# Input-Battery.net
KiCad netlist of a schematic drawn in Altium Designer
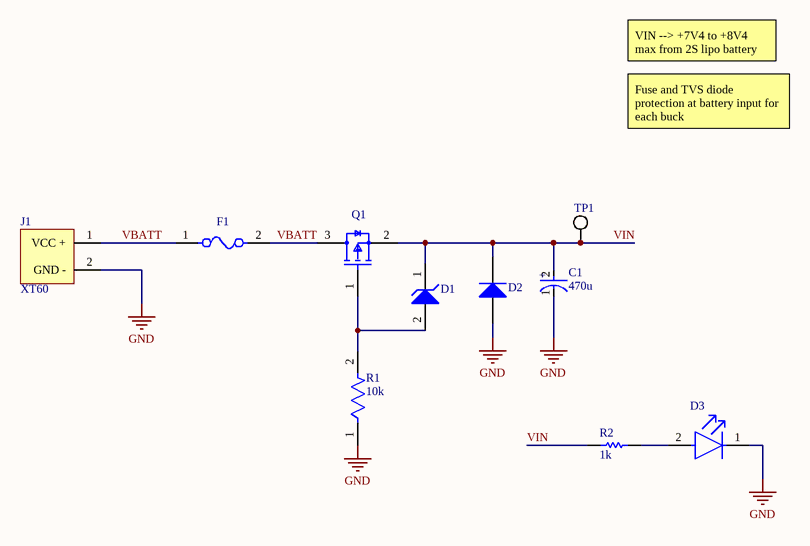
[diagram p0: Input-Battery.SchDoc]

(export (version "E")
  (design (tool "Eeschema 10.0.6"))
  (components
    (comp (ref "C1")
      (value "470u")
      (footprint "FP-RAD-TH-D_10_0_5-L_12_5-MFG")
      (description "Aluminum Electrolytic Capacitors (Radial Lead Type) 470uF ±20% 16V")
      (fields (field (name "TOLERANCE") "20%"))
      (libsource (lib "Altium Content Vault") (part "203bc49f2ac43e59fd269a8c329ed05"))
    )
    (comp (ref "D1")
      (value "MMSZ12T1G")
      (footprint "ONSC-SOD-123-2-425-04_V")
      (description "Zener Voltage Regulator, 500 mW, 2-Pin SOD-123, Pb-Free, Tape and Reel")
      (fields (field (name "MANUFACTURER") "On Semiconductor"))
      (libsource (lib "Altium Content Vault") (part "ONSC-K1A2-2"))
    )
    (comp (ref "D2")
      (value "SMAJ10A-E3/61")
      (footprint "VISH-DO-214AC-2_L")
      (fields (field (name "MANUFACTURER") "Vishay Semiconductor"))
      (libsource (lib "Altium Content Vault") (part "VISH-K1A2-2"))
    )
    (comp (ref "D3")
      (value "598-8270-107F")
      (footprint "FP-598-8270-107F-MFG")
      (description "SM LED 1206 ALINGAP G 7 REEL")
      (libsource (lib "Altium Content Vault") (part "8706943c75ba83719d021d2fdc84c58"))
    )
    (comp (ref "F1")
      (value "0452004.MRL")
      (footprint "FP-0452-MFG")
      (description "FUSE BRD MNT 4A 125VAC/VDC 2SMD")
      (fields
        (field (name "MANUFACTURER") "Littelfuse Inc")
        (field (name "OCTOPART") "https://octopart.com/0452004.mrl-littelfuse-566421")
      )
      (libsource (lib "Altium Content Vault") (part "5bcf9b9f640e542cf0359d10258e979"))
    )
    (comp (ref "J1")
      (value "XT60")
      (footprint "XT60-Footprint-1")
      (description "Connector for Lipo Batteries with XT60 connectors")
      (libsource (lib "University of California, Riverside") (part "XT60"))
    )
    (comp (ref "Q1")
      (value "DMP3099L-13")
      (footprint "FP-SOT23-IPC_A")
      (description "MOSFET P-CH 30V 3.8A SOT23")
      (libsource (lib "Altium Content Vault") (part "638227d500694eacab38e5d89898fd4"))
    )
    (comp (ref "R1")
      (value "10k")
      (footprint "FP-AC1206-MFG")
      (description "AC1206 10KΩ 0.25W 1.00%")
      (fields (field (name "MANUFACTURER PART NUMBER") "AC1206FR-1310KL") (field (name "TOLERANCE") "0.01"))
      (libsource (lib "Altium Content Vault") (part "1029c3af85768c4190bb7ad29bc67b5"))
    )
    (comp (ref "R2")
      (value "1k")
      (footprint "RESC3216X60X45ML10T20")
      (fields (field (name "MANUFACTURER") "Vishay Dale") (field (name "PART NUMBER") "CRCW12061K00JNTA"))
      (libsource (lib "Altium Content Vault") (part "RES"))
    )
    (comp (ref "TP1")
      (value "Test Point")
      (footprint "Test Point")
      (libsource (lib "University of California, Riverside") (part "Test Point"))
    )
  )
  (nets
    (net (code "1") (name "/VBATT") (class "Default")
      (node (ref "F1") (pin "1") (pinfunction "1_1") (pintype "passive"))
      (node (ref "F1") (pin "2") (pinfunction "2_2") (pintype "passive"))
      (node (ref "J1") (pin "1") (pinfunction "VCC_+_1") (pintype "passive"))
      (node (ref "Q1") (pin "3") (pinfunction "D_3") (pintype "passive"))
    )
    (net (code "2") (name "/VIN") (class "Default")
      (node (ref "C1") (pin "2") (pinfunction "A_2") (pintype "passive"))
      (node (ref "D1") (pin "1") (pinfunction "K_1") (pintype "passive"))
      (node (ref "D2") (pin "1") (pinfunction "K_1") (pintype "passive"))
      (node (ref "Q1") (pin "2") (pinfunction "S_2") (pintype "passive"))
      (node (ref "R2") (pin "1") (pinfunction "1_1") (pintype "passive"))
      (node (ref "TP1") (pin "1") (pinfunction "1_1") (pintype "passive"))
    )
    (net (code "3") (name "GND") (class "Default")
      (node (ref "C1") (pin "1") (pinfunction "C_1") (pintype "passive"))
      (node (ref "D2") (pin "2") (pinfunction "A_2") (pintype "passive"))
      (node (ref "D3") (pin "1") (pinfunction "C_1") (pintype "passive"))
      (node (ref "J1") (pin "2") (pinfunction "GND_-_2") (pintype "passive"))
      (node (ref "R1") (pin "1") (pinfunction "1_1") (pintype "passive"))
    )
    (net (code "4") (name "Net-(D1-A)") (class "Default")
      (node (ref "D1") (pin "2") (pinfunction "A_2") (pintype "passive"))
      (node (ref "Q1") (pin "1") (pinfunction "G_1") (pintype "passive"))
      (node (ref "R1") (pin "2") (pinfunction "2_2") (pintype "passive"))
    )
    (net (code "5") (name "Net-(D3-A)") (class "Default")
      (node (ref "D3") (pin "2") (pinfunction "A_2") (pintype "passive"))
      (node (ref "R2") (pin "2") (pinfunction "2_2") (pintype "passive"))
    )
  )
)
